# waterlevel.net
KiCad netlist of a schematic drawn in EAGLE
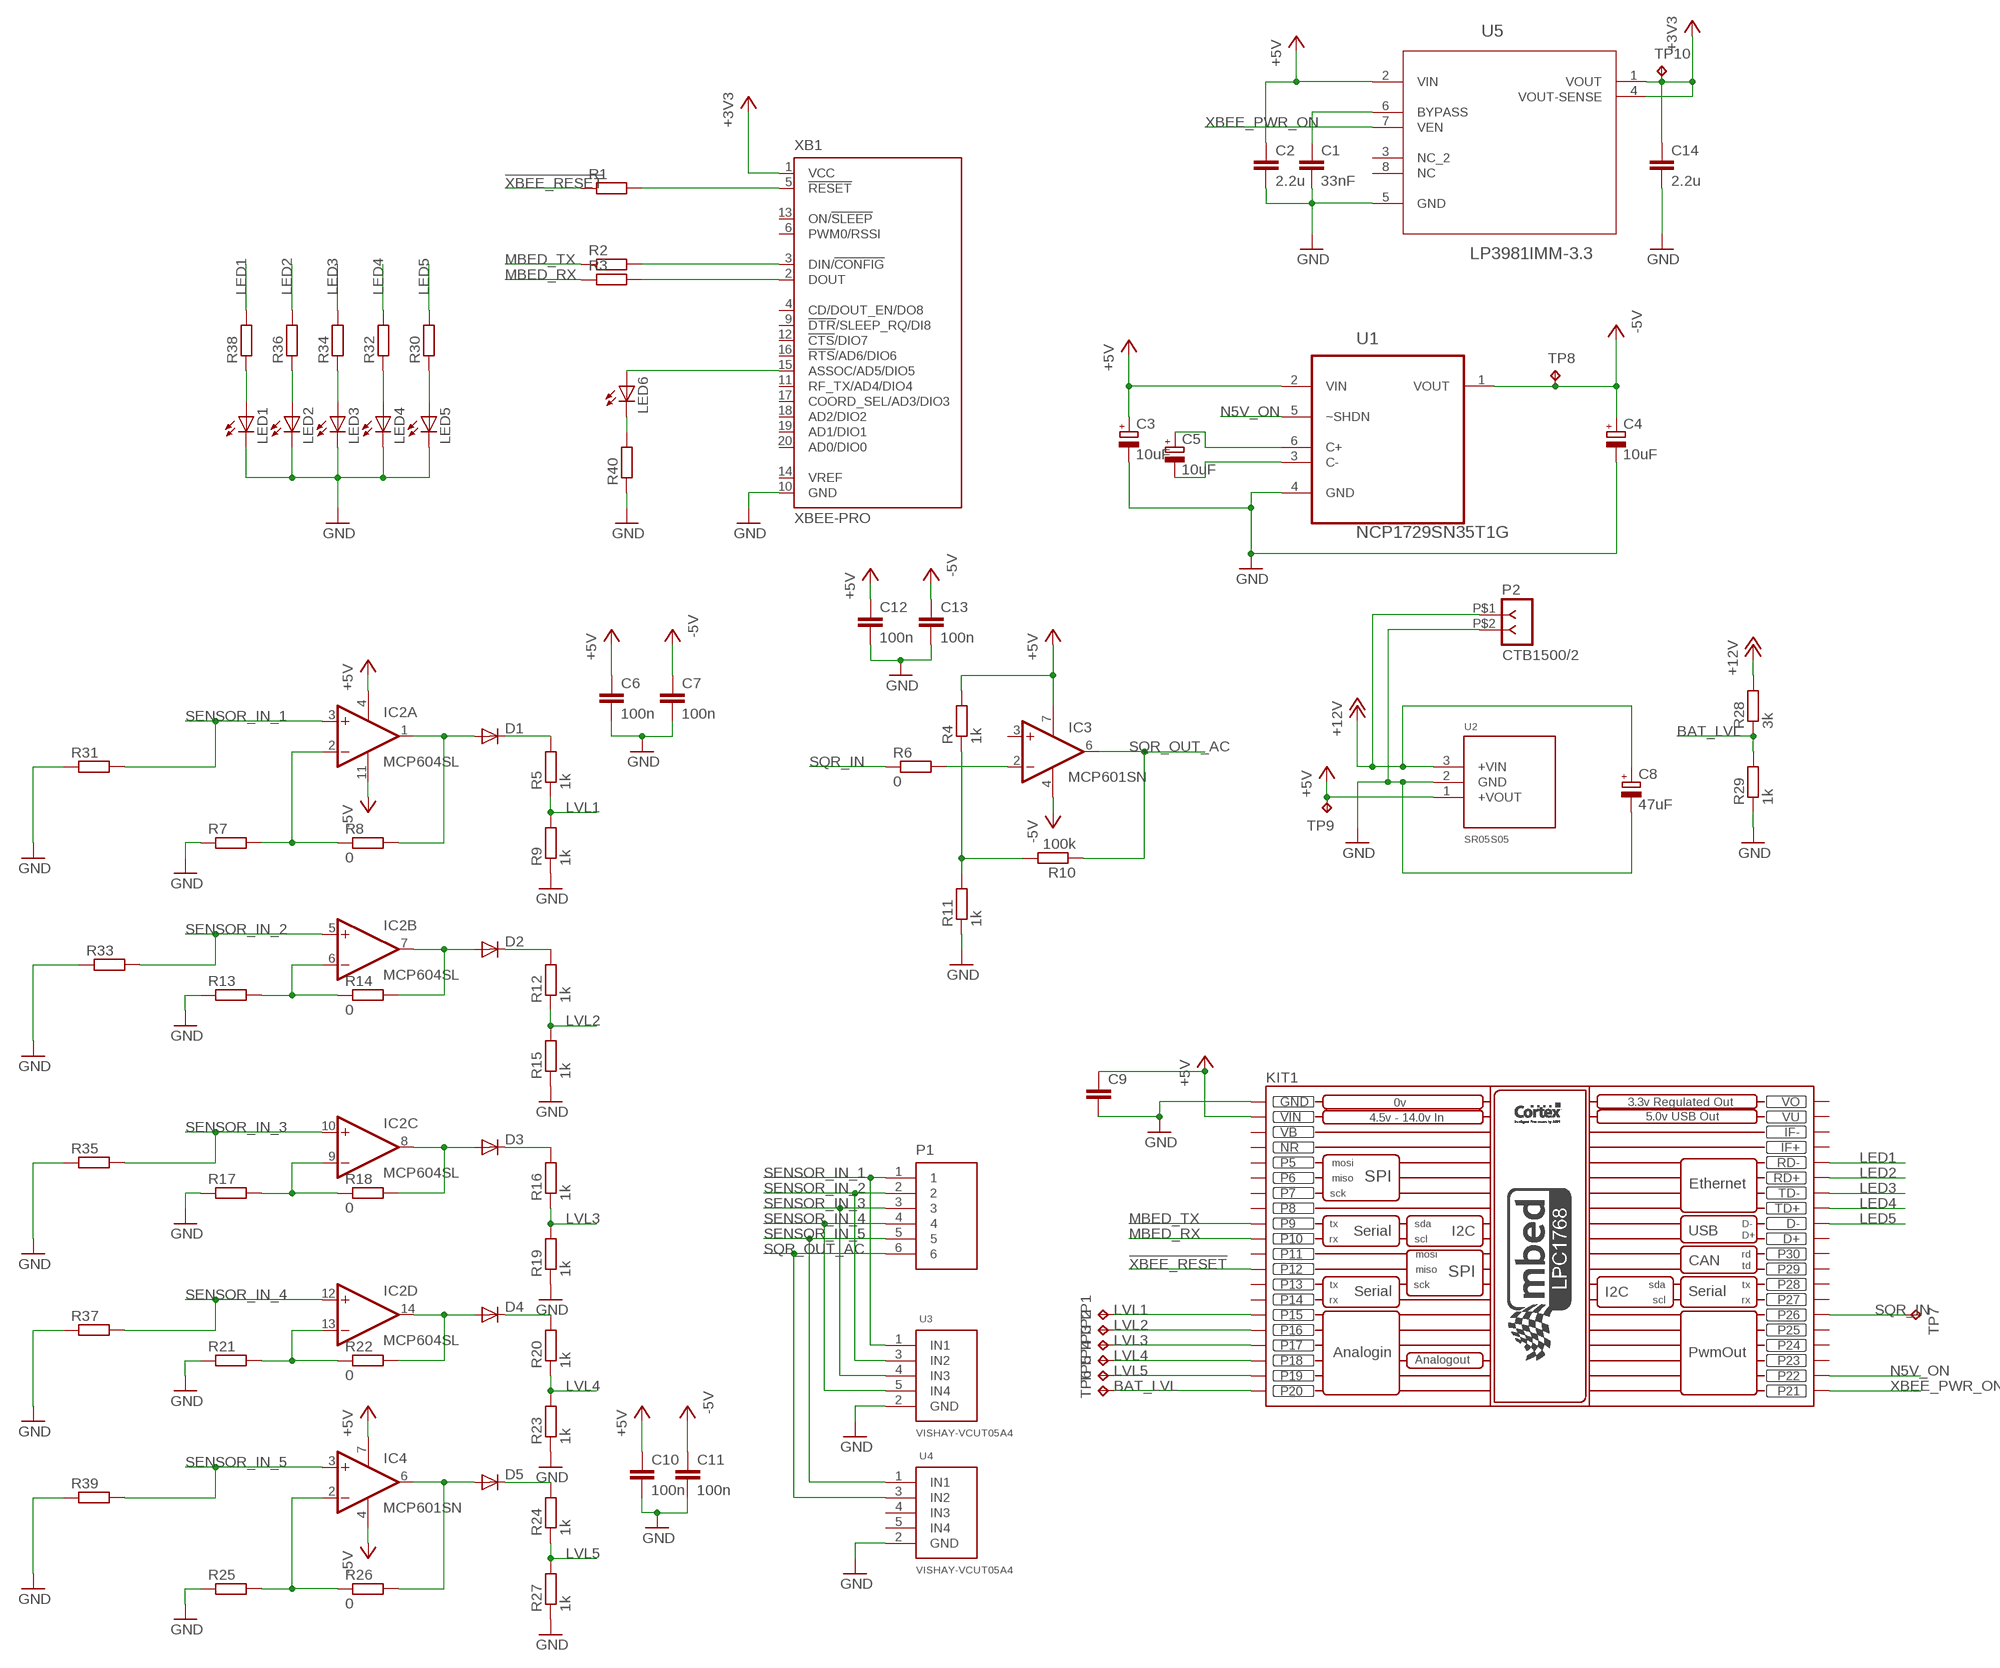
[diagram p0: schematic, sheet 1]

(export (version "E")
  (design (tool "Eeschema 10.0.6"))
  (components
    (comp (ref "C1")
      (value "33nF")
      (footprint "eagle-import:C0603")
      (libsource (lib "eagle-import") (part "C-EUC0603"))
    )
    (comp (ref "C2")
      (value "2.2u")
      (footprint "eagle-import:C0603")
      (libsource (lib "eagle-import") (part "C-EUC0603"))
    )
    (comp (ref "C3")
      (value "10uF")
      (footprint "eagle-import:D_7343-31R")
      (libsource (lib "eagle-import") (part "CPOL-EUD/7343-31R"))
    )
    (comp (ref "C4")
      (value "10uF")
      (footprint "eagle-import:D_7343-31R")
      (libsource (lib "eagle-import") (part "CPOL-EUD/7343-31R"))
    )
    (comp (ref "C5")
      (value "10uF")
      (footprint "eagle-import:D_7343-31R")
      (libsource (lib "eagle-import") (part "CPOL-EUD/7343-31R"))
    )
    (comp (ref "C6")
      (value "100n")
      (footprint "eagle-import:C1206")
      (libsource (lib "eagle-import") (part "C-EUC1206"))
    )
    (comp (ref "C7")
      (value "100n")
      (footprint "eagle-import:C1206")
      (libsource (lib "eagle-import") (part "C-EUC1206"))
    )
    (comp (ref "C8")
      (value "47uF")
      (footprint "eagle-import:D_7343-31R")
      (libsource (lib "eagle-import") (part "CPOL-EUD/7343-31R"))
    )
    (comp (ref "C9")
      (value "C-EUC1206")
      (footprint "eagle-import:C1206")
      (libsource (lib "eagle-import") (part "C-EUC1206"))
    )
    (comp (ref "C10")
      (value "100n")
      (footprint "eagle-import:C1206")
      (libsource (lib "eagle-import") (part "C-EUC1206"))
    )
    (comp (ref "C11")
      (value "100n")
      (footprint "eagle-import:C1206")
      (libsource (lib "eagle-import") (part "C-EUC1206"))
    )
    (comp (ref "C12")
      (value "100n")
      (footprint "eagle-import:C1206")
      (libsource (lib "eagle-import") (part "C-EUC1206"))
    )
    (comp (ref "C13")
      (value "100n")
      (footprint "eagle-import:C1206")
      (libsource (lib "eagle-import") (part "C-EUC1206"))
    )
    (comp (ref "C14")
      (value "2.2u")
      (footprint "eagle-import:C0603")
      (libsource (lib "eagle-import") (part "C-EUC0603"))
    )
    (comp (ref "D1")
      (value "DIODE-SOD323-R")
      (footprint "eagle-import:SOD323-R")
      (fields (field (name "PART") "RB751V40"))
      (libsource (lib "eagle-import") (part "DIODE-SOD323-R"))
    )
    (comp (ref "D2")
      (value "DIODE-SOD323-R")
      (footprint "eagle-import:SOD323-R")
      (fields (field (name "PART") "RB751V40"))
      (libsource (lib "eagle-import") (part "DIODE-SOD323-R"))
    )
    (comp (ref "D3")
      (value "DIODE-SOD323-R")
      (footprint "eagle-import:SOD323-R")
      (fields (field (name "PART") "RB751V40"))
      (libsource (lib "eagle-import") (part "DIODE-SOD323-R"))
    )
    (comp (ref "D4")
      (value "DIODE-SOD323-R")
      (footprint "eagle-import:SOD323-R")
      (fields (field (name "PART") "RB751V40"))
      (libsource (lib "eagle-import") (part "DIODE-SOD323-R"))
    )
    (comp (ref "D5")
      (value "DIODE-SOD323-R")
      (footprint "eagle-import:SOD323-R")
      (fields (field (name "PART") "RB751V40"))
      (libsource (lib "eagle-import") (part "DIODE-SOD323-R"))
    )
    (comp (ref "IC2")
      (value "MCP604SL")
      (footprint "eagle-import:SO14")
      (libsource (lib "eagle-import") (part "MCP604SL"))
    )
    (comp (ref "IC3")
      (value "MCP601SN")
      (footprint "eagle-import:SO08")
      (libsource (lib "eagle-import") (part "MCP601SN"))
    )
    (comp (ref "IC4")
      (value "MCP601SN")
      (footprint "eagle-import:SO08")
      (libsource (lib "eagle-import") (part "MCP601SN"))
    )
    (comp (ref "KIT1")
      (value "MBED_NXP_LPC1768")
      (footprint "eagle-import:MBED-KIT")
      (libsource (lib "eagle-import") (part "MBED_NXP_LPC1768"))
    )
    (comp (ref "LED1")
      (value "LEDCHIPLED_0805")
      (footprint "eagle-import:CHIPLED_0805")
      (libsource (lib "eagle-import") (part "LEDCHIPLED_0805"))
    )
    (comp (ref "LED2")
      (value "LEDCHIPLED_0805")
      (footprint "eagle-import:CHIPLED_0805")
      (libsource (lib "eagle-import") (part "LEDCHIPLED_0805"))
    )
    (comp (ref "LED3")
      (value "LEDCHIPLED_0805")
      (footprint "eagle-import:CHIPLED_0805")
      (libsource (lib "eagle-import") (part "LEDCHIPLED_0805"))
    )
    (comp (ref "LED4")
      (value "LEDCHIPLED_0805")
      (footprint "eagle-import:CHIPLED_0805")
      (libsource (lib "eagle-import") (part "LEDCHIPLED_0805"))
    )
    (comp (ref "LED5")
      (value "LEDCHIPLED_0805")
      (footprint "eagle-import:CHIPLED_0805")
      (libsource (lib "eagle-import") (part "LEDCHIPLED_0805"))
    )
    (comp (ref "LED6")
      (value "LEDCHIPLED_0805")
      (footprint "eagle-import:CHIPLED_0805")
      (libsource (lib "eagle-import") (part "LEDCHIPLED_0805"))
    )
    (comp (ref "P1")
      (value "CAMDEN-CTB5000/6")
      (footprint "eagle-import:CAMDEN-CTB5000")
      (libsource (lib "eagle-import") (part "CAMDEN-CTB5000/6"))
    )
    (comp (ref "P2")
      (value "CTB1500/2")
      (footprint "eagle-import:CTB1500-2")
      (libsource (lib "eagle-import") (part "CTB1500/2"))
    )
    (comp (ref "R1")
      (value "R-EU_R0603")
      (footprint "eagle-import:R0603")
      (libsource (lib "eagle-import") (part "R-EU_R0603"))
    )
    (comp (ref "R2")
      (value "R-EU_R0603")
      (footprint "eagle-import:R0603")
      (libsource (lib "eagle-import") (part "R-EU_R0603"))
    )
    (comp (ref "R3")
      (value "R-EU_R0603")
      (footprint "eagle-import:R0603")
      (libsource (lib "eagle-import") (part "R-EU_R0603"))
    )
    (comp (ref "R4")
      (value "1k")
      (footprint "eagle-import:R0805")
      (libsource (lib "eagle-import") (part "R-EU_R0805"))
    )
    (comp (ref "R5")
      (value "1k")
      (footprint "eagle-import:R0805")
      (libsource (lib "eagle-import") (part "R-EU_R0805"))
    )
    (comp (ref "R6")
      (value "0")
      (footprint "eagle-import:R0603")
      (libsource (lib "eagle-import") (part "R-EU_R0603"))
    )
    (comp (ref "R7")
      (value "R-EU_R0603")
      (footprint "eagle-import:R0603")
      (libsource (lib "eagle-import") (part "R-EU_R0603"))
    )
    (comp (ref "R8")
      (value "0")
      (footprint "eagle-import:R0603")
      (libsource (lib "eagle-import") (part "R-EU_R0603"))
    )
    (comp (ref "R9")
      (value "1k")
      (footprint "eagle-import:R0805")
      (libsource (lib "eagle-import") (part "R-EU_R0805"))
    )
    (comp (ref "R10")
      (value "100k")
      (footprint "eagle-import:R0805")
      (libsource (lib "eagle-import") (part "R-EU_R0805"))
    )
    (comp (ref "R11")
      (value "1k")
      (footprint "eagle-import:R0805")
      (libsource (lib "eagle-import") (part "R-EU_R0805"))
    )
    (comp (ref "R12")
      (value "1k")
      (footprint "eagle-import:R0805")
      (libsource (lib "eagle-import") (part "R-EU_R0805"))
    )
    (comp (ref "R13")
      (value "R-EU_R0603")
      (footprint "eagle-import:R0603")
      (libsource (lib "eagle-import") (part "R-EU_R0603"))
    )
    (comp (ref "R14")
      (value "0")
      (footprint "eagle-import:R0603")
      (libsource (lib "eagle-import") (part "R-EU_R0603"))
    )
    (comp (ref "R15")
      (value "1k")
      (footprint "eagle-import:R0805")
      (libsource (lib "eagle-import") (part "R-EU_R0805"))
    )
    (comp (ref "R16")
      (value "1k")
      (footprint "eagle-import:R0805")
      (libsource (lib "eagle-import") (part "R-EU_R0805"))
    )
    (comp (ref "R17")
      (value "R-EU_R0603")
      (footprint "eagle-import:R0603")
      (libsource (lib "eagle-import") (part "R-EU_R0603"))
    )
    (comp (ref "R18")
      (value "0")
      (footprint "eagle-import:R0603")
      (libsource (lib "eagle-import") (part "R-EU_R0603"))
    )
    (comp (ref "R19")
      (value "1k")
      (footprint "eagle-import:R0805")
      (libsource (lib "eagle-import") (part "R-EU_R0805"))
    )
    (comp (ref "R20")
      (value "1k")
      (footprint "eagle-import:R0805")
      (libsource (lib "eagle-import") (part "R-EU_R0805"))
    )
    (comp (ref "R21")
      (value "R-EU_R0603")
      (footprint "eagle-import:R0603")
      (libsource (lib "eagle-import") (part "R-EU_R0603"))
    )
    (comp (ref "R22")
      (value "0")
      (footprint "eagle-import:R0603")
      (libsource (lib "eagle-import") (part "R-EU_R0603"))
    )
    (comp (ref "R23")
      (value "1k")
      (footprint "eagle-import:R0805")
      (libsource (lib "eagle-import") (part "R-EU_R0805"))
    )
    (comp (ref "R24")
      (value "1k")
      (footprint "eagle-import:R0805")
      (libsource (lib "eagle-import") (part "R-EU_R0805"))
    )
    (comp (ref "R25")
      (value "R-EU_R0603")
      (footprint "eagle-import:R0603")
      (libsource (lib "eagle-import") (part "R-EU_R0603"))
    )
    (comp (ref "R26")
      (value "0")
      (footprint "eagle-import:R0603")
      (libsource (lib "eagle-import") (part "R-EU_R0603"))
    )
    (comp (ref "R27")
      (value "1k")
      (footprint "eagle-import:R0805")
      (libsource (lib "eagle-import") (part "R-EU_R0805"))
    )
    (comp (ref "R28")
      (value "3k")
      (footprint "eagle-import:R0805")
      (libsource (lib "eagle-import") (part "R-EU_R0805"))
    )
    (comp (ref "R29")
      (value "1k")
      (footprint "eagle-import:R0805")
      (libsource (lib "eagle-import") (part "R-EU_R0805"))
    )
    (comp (ref "R30")
      (value "R-EU_R0603")
      (footprint "eagle-import:R0603")
      (libsource (lib "eagle-import") (part "R-EU_R0603"))
    )
    (comp (ref "R31")
      (value "R-EU_R0805")
      (footprint "eagle-import:R0805")
      (libsource (lib "eagle-import") (part "R-EU_R0805"))
    )
    (comp (ref "R32")
      (value "R-EU_R0603")
      (footprint "eagle-import:R0603")
      (libsource (lib "eagle-import") (part "R-EU_R0603"))
    )
    (comp (ref "R33")
      (value "R-EU_R0805")
      (footprint "eagle-import:R0805")
      (libsource (lib "eagle-import") (part "R-EU_R0805"))
    )
    (comp (ref "R34")
      (value "R-EU_R0603")
      (footprint "eagle-import:R0603")
      (libsource (lib "eagle-import") (part "R-EU_R0603"))
    )
    (comp (ref "R35")
      (value "R-EU_R0805")
      (footprint "eagle-import:R0805")
      (libsource (lib "eagle-import") (part "R-EU_R0805"))
    )
    (comp (ref "R36")
      (value "R-EU_R0603")
      (footprint "eagle-import:R0603")
      (libsource (lib "eagle-import") (part "R-EU_R0603"))
    )
    (comp (ref "R37")
      (value "R-EU_R0805")
      (footprint "eagle-import:R0805")
      (libsource (lib "eagle-import") (part "R-EU_R0805"))
    )
    (comp (ref "R38")
      (value "R-EU_R0603")
      (footprint "eagle-import:R0603")
      (libsource (lib "eagle-import") (part "R-EU_R0603"))
    )
    (comp (ref "R39")
      (value "R-EU_R0805")
      (footprint "eagle-import:R0805")
      (libsource (lib "eagle-import") (part "R-EU_R0805"))
    )
    (comp (ref "R40")
      (value "R-EU_R0603")
      (footprint "eagle-import:R0603")
      (libsource (lib "eagle-import") (part "R-EU_R0603"))
    )
    (comp (ref "TP1")
      (value "TPTP13R")
      (footprint "eagle-import:TP13R")
      (libsource (lib "eagle-import") (part "TPTP13R"))
    )
    (comp (ref "TP2")
      (value "TPTP13R")
      (footprint "eagle-import:TP13R")
      (libsource (lib "eagle-import") (part "TPTP13R"))
    )
    (comp (ref "TP3")
      (value "TPTP13R")
      (footprint "eagle-import:TP13R")
      (libsource (lib "eagle-import") (part "TPTP13R"))
    )
    (comp (ref "TP4")
      (value "TPTP13R")
      (footprint "eagle-import:TP13R")
      (libsource (lib "eagle-import") (part "TPTP13R"))
    )
    (comp (ref "TP5")
      (value "TPTP13R")
      (footprint "eagle-import:TP13R")
      (libsource (lib "eagle-import") (part "TPTP13R"))
    )
    (comp (ref "TP6")
      (value "TPTP13R")
      (footprint "eagle-import:TP13R")
      (libsource (lib "eagle-import") (part "TPTP13R"))
    )
    (comp (ref "TP7")
      (value "TPTP13R")
      (footprint "eagle-import:TP13R")
      (libsource (lib "eagle-import") (part "TPTP13R"))
    )
    (comp (ref "TP8")
      (value "TPTP13R")
      (footprint "eagle-import:TP13R")
      (libsource (lib "eagle-import") (part "TPTP13R"))
    )
    (comp (ref "TP9")
      (value "TPTP13R")
      (footprint "eagle-import:TP13R")
      (libsource (lib "eagle-import") (part "TPTP13R"))
    )
    (comp (ref "TP10")
      (value "TPTP13R")
      (footprint "eagle-import:TP13R")
      (libsource (lib "eagle-import") (part "TPTP13R"))
    )
    (comp (ref "U1")
      (value "NCP1729SN35T1G")
      (footprint "eagle-import:SOP95P275X110-6N")
      (libsource (lib "eagle-import") (part "NCP1729SN35T1G"))
    )
    (comp (ref "U2")
      (value "SR05S05")
      (footprint "eagle-import:XP-SR-SERIES")
      (libsource (lib "eagle-import") (part "SR05S05"))
    )
    (comp (ref "U3")
      (value "VISHAY-VCUT05A4")
      (footprint "eagle-import:SOT23-5")
      (libsource (lib "eagle-import") (part "VISHAY-VCUT05A4"))
    )
    (comp (ref "U4")
      (value "VISHAY-VCUT05A4")
      (footprint "eagle-import:SOT23-5")
      (libsource (lib "eagle-import") (part "VISHAY-VCUT05A4"))
    )
    (comp (ref "U5")
      (value "LP3981IMM-3.3")
      (footprint "eagle-import:SOP65P490X110-8N")
      (libsource (lib "eagle-import") (part "LP3981IMM-3.3"))
    )
    (comp (ref "XB1")
      (value "XBEE-PRO")
      (footprint "eagle-import:XBEE-PRO")
      (fields (field (name "MPN") "XBP24-AWI-001"))
      (libsource (lib "eagle-import") (part "XBEE-PRO"))
    )
  )
  (nets
    (net (code "1") (name "+3V3") (class "Default")
      (node (ref "C14") (pin "1") (pinfunction "1_1") (pintype "passive"))
      (node (ref "TP10") (pin "TP") (pinfunction "TP_TP") (pintype "input"))
      (node (ref "U5") (pin "1") (pinfunction "VOUT_1") (pintype "output"))
      (node (ref "U5") (pin "4") (pinfunction "VOUT-SENSE_4") (pintype "output"))
      (node (ref "XB1") (pin "1") (pinfunction "VCC_1") (pintype "power_in"))
    )
    (net (code "2") (name "+5V") (class "Default")
      (node (ref "C10") (pin "1") (pinfunction "1_1") (pintype "passive"))
      (node (ref "C12") (pin "1") (pinfunction "1_1") (pintype "passive"))
      (node (ref "C2") (pin "1") (pinfunction "1_1") (pintype "passive"))
      (node (ref "C3") (pin "+") (pinfunction "+_+") (pintype "passive"))
      (node (ref "C6") (pin "1") (pinfunction "1_1") (pintype "passive"))
      (node (ref "C9") (pin "1") (pinfunction "1_1") (pintype "passive"))
      (node (ref "IC2") (pin "4") (pinfunction "V+_4") (pintype "power_in"))
      (node (ref "IC3") (pin "7") (pinfunction "V+_7") (pintype "power_in"))
      (node (ref "IC4") (pin "7") (pinfunction "V+_7") (pintype "power_in"))
      (node (ref "KIT1") (pin "VIN") (pinfunction "VIN_VIN") (pintype "power_in"))
      (node (ref "R4") (pin "2") (pinfunction "2_2") (pintype "passive"))
      (node (ref "TP9") (pin "TP") (pinfunction "TP_TP") (pintype "input"))
      (node (ref "U1") (pin "2") (pinfunction "VIN_2") (pintype "power_in"))
      (node (ref "U2") (pin "1") (pinfunction "+VOUT_1") (pintype "bidirectional"))
      (node (ref "U5") (pin "2") (pinfunction "VIN_2") (pintype "input"))
    )
    (net (code "3") (name "+12V") (class "Default")
      (node (ref "C8") (pin "+") (pinfunction "+_+") (pintype "passive"))
      (node (ref "P2") (pin "P$1") (pinfunction "1_P$1") (pintype "passive"))
      (node (ref "R28") (pin "2") (pinfunction "2_2") (pintype "passive"))
      (node (ref "U2") (pin "3") (pinfunction "+VIN_3") (pintype "bidirectional"))
    )
    (net (code "4") (name "-5V") (class "Default")
      (node (ref "C11") (pin "1") (pinfunction "1_1") (pintype "passive"))
      (node (ref "C13") (pin "1") (pinfunction "1_1") (pintype "passive"))
      (node (ref "C4") (pin "+") (pinfunction "+_+") (pintype "passive"))
      (node (ref "C7") (pin "1") (pinfunction "1_1") (pintype "passive"))
      (node (ref "IC2") (pin "11") (pinfunction "V-_11") (pintype "power_in"))
      (node (ref "IC3") (pin "4") (pinfunction "V-_4") (pintype "power_in"))
      (node (ref "IC4") (pin "4") (pinfunction "V-_4") (pintype "power_in"))
      (node (ref "TP8") (pin "TP") (pinfunction "TP_TP") (pintype "input"))
      (node (ref "U1") (pin "1") (pinfunction "VOUT_1") (pintype "output"))
    )
    (net (code "5") (name "/BAT_LVL") (class "Default")
      (node (ref "KIT1") (pin "P$20") (pinfunction "P20_P$20") (pintype "bidirectional"))
      (node (ref "R28") (pin "1") (pinfunction "1_1") (pintype "passive"))
      (node (ref "R29") (pin "2") (pinfunction "2_2") (pintype "passive"))
      (node (ref "TP6") (pin "TP") (pinfunction "TP_TP") (pintype "input"))
    )
    (net (code "6") (name "/LED1") (class "Default")
      (node (ref "KIT1") (pin "RD-") (pinfunction "RD-_RD-") (pintype "bidirectional"))
      (node (ref "R38") (pin "2") (pinfunction "2_2") (pintype "passive"))
    )
    (net (code "7") (name "/LED2") (class "Default")
      (node (ref "KIT1") (pin "RD+") (pinfunction "RD+_RD+") (pintype "bidirectional"))
      (node (ref "R36") (pin "2") (pinfunction "2_2") (pintype "passive"))
    )
    (net (code "8") (name "/LED3") (class "Default")
      (node (ref "KIT1") (pin "TD-") (pinfunction "TD-_TD-") (pintype "bidirectional"))
      (node (ref "R34") (pin "2") (pinfunction "2_2") (pintype "passive"))
    )
    (net (code "9") (name "/LED4") (class "Default")
      (node (ref "KIT1") (pin "TD+") (pinfunction "TD+_TD+") (pintype "bidirectional"))
      (node (ref "R32") (pin "2") (pinfunction "2_2") (pintype "passive"))
    )
    (net (code "10") (name "/LED5") (class "Default")
      (node (ref "KIT1") (pin "D-") (pinfunction "D-_D-") (pintype "bidirectional"))
      (node (ref "R30") (pin "2") (pinfunction "2_2") (pintype "passive"))
    )
    (net (code "11") (name "/LVL1") (class "Default")
      (node (ref "KIT1") (pin "P$15") (pinfunction "P15_P$15") (pintype "bidirectional"))
      (node (ref "R5") (pin "1") (pinfunction "1_1") (pintype "passive"))
      (node (ref "R9") (pin "2") (pinfunction "2_2") (pintype "passive"))
      (node (ref "TP1") (pin "TP") (pinfunction "TP_TP") (pintype "input"))
    )
    (net (code "12") (name "/LVL2") (class "Default")
      (node (ref "KIT1") (pin "P$16") (pinfunction "P16_P$16") (pintype "bidirectional"))
      (node (ref "R12") (pin "1") (pinfunction "1_1") (pintype "passive"))
      (node (ref "R15") (pin "2") (pinfunction "2_2") (pintype "passive"))
      (node (ref "TP2") (pin "TP") (pinfunction "TP_TP") (pintype "input"))
    )
    (net (code "13") (name "/LVL3") (class "Default")
      (node (ref "KIT1") (pin "P$17") (pinfunction "P17_P$17") (pintype "bidirectional"))
      (node (ref "R16") (pin "1") (pinfunction "1_1") (pintype "passive"))
      (node (ref "R19") (pin "2") (pinfunction "2_2") (pintype "passive"))
      (node (ref "TP3") (pin "TP") (pinfunction "TP_TP") (pintype "input"))
    )
    (net (code "14") (name "/LVL4") (class "Default")
      (node (ref "KIT1") (pin "P$18") (pinfunction "P18_P$18") (pintype "bidirectional"))
      (node (ref "R20") (pin "1") (pinfunction "1_1") (pintype "passive"))
      (node (ref "R23") (pin "2") (pinfunction "2_2") (pintype "passive"))
      (node (ref "TP4") (pin "TP") (pinfunction "TP_TP") (pintype "input"))
    )
    (net (code "15") (name "/LVL5") (class "Default")
      (node (ref "KIT1") (pin "P$19") (pinfunction "P19_P$19") (pintype "bidirectional"))
      (node (ref "R24") (pin "1") (pinfunction "1_1") (pintype "passive"))
      (node (ref "R27") (pin "2") (pinfunction "2_2") (pintype "passive"))
      (node (ref "TP5") (pin "TP") (pinfunction "TP_TP") (pintype "input"))
    )
    (net (code "16") (name "/MBED_RX") (class "Default")
      (node (ref "KIT1") (pin "P$10") (pinfunction "P10_P$10") (pintype "bidirectional"))
      (node (ref "R3") (pin "1") (pinfunction "1_1") (pintype "passive"))
    )
    (net (code "17") (name "/MBED_TX") (class "Default")
      (node (ref "KIT1") (pin "P$9") (pinfunction "P9_P$9") (pintype "bidirectional"))
      (node (ref "R2") (pin "1") (pinfunction "1_1") (pintype "passive"))
    )
    (net (code "18") (name "/N5V_ON") (class "Default")
      (node (ref "KIT1") (pin "P$22") (pinfunction "P22_P$22") (pintype "bidirectional"))
      (node (ref "U1") (pin "5") (pinfunction "~{SHDN}_5") (pintype "input"))
    )
    (net (code "19") (name "/NR") (class "Default")
      (node (ref "KIT1") (pin "NR") (pinfunction "NR_NR") (pintype "power_in"))
    )
    (net (code "20") (name "/SENSOR_IN_1") (class "Default")
      (node (ref "IC2") (pin "3") (pinfunction "+IN_3") (pintype "input"))
      (node (ref "P1") (pin "1") (pinfunction "1_1") (pintype "bidirectional"))
      (node (ref "R31") (pin "2") (pinfunction "2_2") (pintype "passive"))
      (node (ref "U3") (pin "1") (pinfunction "IN1_1") (pintype "bidirectional"))
    )
    (net (code "21") (name "/SENSOR_IN_2") (class "Default")
      (node (ref "IC2") (pin "5") (pinfunction "+IN_5") (pintype "input"))
      (node (ref "P1") (pin "2") (pinfunction "2_2") (pintype "bidirectional"))
      (node (ref "R33") (pin "2") (pinfunction "2_2") (pintype "passive"))
      (node (ref "U3") (pin "3") (pinfunction "IN2_3") (pintype "bidirectional"))
    )
    (net (code "22") (name "/SENSOR_IN_3") (class "Default")
      (node (ref "IC2") (pin "10") (pinfunction "+IN_10") (pintype "input"))
      (node (ref "P1") (pin "3") (pinfunction "3_3") (pintype "bidirectional"))
      (node (ref "R35") (pin "2") (pinfunction "2_2") (pintype "passive"))
      (node (ref "U3") (pin "4") (pinfunction "IN3_4") (pintype "bidirectional"))
    )
    (net (code "23") (name "/SENSOR_IN_4") (class "Default")
      (node (ref "IC2") (pin "12") (pinfunction "+IN_12") (pintype "input"))
      (node (ref "P1") (pin "4") (pinfunction "4_4") (pintype "bidirectional"))
      (node (ref "R37") (pin "2") (pinfunction "2_2") (pintype "passive"))
      (node (ref "U3") (pin "5") (pinfunction "IN4_5") (pintype "bidirectional"))
    )
    (net (code "24") (name "/SENSOR_IN_5") (class "Default")
      (node (ref "IC4") (pin "3") (pinfunction "+IN_3") (pintype "input"))
      (node (ref "P1") (pin "5") (pinfunction "5_5") (pintype "bidirectional"))
      (node (ref "R39") (pin "2") (pinfunction "2_2") (pintype "passive"))
      (node (ref "U4") (pin "1") (pinfunction "IN1_1") (pintype "bidirectional"))
    )
    (net (code "25") (name "/SQR_IN") (class "Default")
      (node (ref "KIT1") (pin "P$26") (pinfunction "P26_P$26") (pintype "bidirectional"))
      (node (ref "R6") (pin "1") (pinfunction "1_1") (pintype "passive"))
      (node (ref "TP7") (pin "TP") (pinfunction "TP_TP") (pintype "input"))
    )
    (net (code "26") (name "/SQR_OUT_AC") (class "Default")
      (node (ref "IC3") (pin "6") (pinfunction "OUT_6") (pintype "output"))
      (node (ref "P1") (pin "6") (pinfunction "6_6") (pintype "bidirectional"))
      (node (ref "R10") (pin "1") (pinfunction "1_1") (pintype "passive"))
      (node (ref "U4") (pin "3") (pinfunction "IN2_3") (pintype "bidirectional"))
    )
    (net (code "27") (name "/VB") (class "Default")
      (node (ref "KIT1") (pin "VB") (pinfunction "VB_VB") (pintype "power_in"))
    )
    (net (code "28") (name "/VO") (class "Default")
      (node (ref "KIT1") (pin "VOUT") (pinfunction "VO_VOUT") (pintype "power_in"))
    )
    (net (code "29") (name "/VU") (class "Default")
      (node (ref "KIT1") (pin "VU") (pinfunction "VU_VU") (pintype "power_in"))
    )
    (net (code "30") (name "/XBEE_PWR_ON") (class "Default")
      (node (ref "KIT1") (pin "P$21") (pinfunction "P21_P$21") (pintype "bidirectional"))
      (node (ref "U5") (pin "7") (pinfunction "VEN_7") (pintype "input"))
    )
    (net (code "31") (name "/~{XBEE_RESET}") (class "Default")
      (node (ref "KIT1") (pin "P$12") (pinfunction "P12_P$12") (pintype "bidirectional"))
      (node (ref "R1") (pin "1") (pinfunction "1_1") (pintype "passive"))
    )
    (net (code "32") (name "GND") (class "Default")
      (node (ref "C1") (pin "2") (pinfunction "2_2") (pintype "passive"))
      (node (ref "C10") (pin "2") (pinfunction "2_2") (pintype "passive"))
      (node (ref "C11") (pin "2") (pinfunction "2_2") (pintype "passive"))
      (node (ref "C12") (pin "2") (pinfunction "2_2") (pintype "passive"))
      (node (ref "C13") (pin "2") (pinfunction "2_2") (pintype "passive"))
      (node (ref "C14") (pin "2") (pinfunction "2_2") (pintype "passive"))
      (node (ref "C2") (pin "2") (pinfunction "2_2") (pintype "passive"))
      (node (ref "C3") (pin "-") (pinfunction "-_-") (pintype "passive"))
      (node (ref "C4") (pin "-") (pinfunction "-_-") (pintype "passive"))
      (node (ref "C6") (pin "2") (pinfunction "2_2") (pintype "passive"))
      (node (ref "C7") (pin "2") (pinfunction "2_2") (pintype "passive"))
      (node (ref "C8") (pin "-") (pinfunction "-_-") (pintype "passive"))
      (node (ref "C9") (pin "2") (pinfunction "2_2") (pintype "passive"))
      (node (ref "KIT1") (pin "GND") (pinfunction "GND_GND") (pintype "power_in"))
      (node (ref "LED1") (pin "C") (pinfunction "C_C") (pintype "passive"))
      (node (ref "LED2") (pin "C") (pinfunction "C_C") (pintype "passive"))
      (node (ref "LED3") (pin "C") (pinfunction "C_C") (pintype "passive"))
      (node (ref "LED4") (pin "C") (pinfunction "C_C") (pintype "passive"))
      (node (ref "LED5") (pin "C") (pinfunction "C_C") (pintype "passive"))
      (node (ref "P2") (pin "P$2") (pinfunction "2_P$2") (pintype "passive"))
      (node (ref "R11") (pin "1") (pinfunction "1_1") (pintype "passive"))
      (node (ref "R13") (pin "1") (pinfunction "1_1") (pintype "passive"))
      (node (ref "R15") (pin "1") (pinfunction "1_1") (pintype "passive"))
      (node (ref "R17") (pin "1") (pinfunction "1_1") (pintype "passive"))
      (node (ref "R19") (pin "1") (pinfunction "1_1") (pintype "passive"))
      (node (ref "R21") (pin "1") (pinfunction "1_1") (pintype "passive"))
      (node (ref "R23") (pin "1") (pinfunction "1_1") (pintype "passive"))
      (node (ref "R25") (pin "1") (pinfunction "1_1") (pintype "passive"))
      (node (ref "R27") (pin "1") (pinfunction "1_1") (pintype "passive"))
      (node (ref "R29") (pin "1") (pinfunction "1_1") (pintype "passive"))
      (node (ref "R31") (pin "1") (pinfunction "1_1") (pintype "passive"))
      (node (ref "R33") (pin "1") (pinfunction "1_1") (pintype "passive"))
      (node (ref "R35") (pin "1") (pinfunction "1_1") (pintype "passive"))
      (node (ref "R37") (pin "1") (pinfunction "1_1") (pintype "passive"))
      (node (ref "R39") (pin "1") (pinfunction "1_1") (pintype "passive"))
      (node (ref "R40") (pin "1") (pinfunction "1_1") (pintype "passive"))
      (node (ref "R7") (pin "1") (pinfunction "1_1") (pintype "passive"))
      (node (ref "R9") (pin "1") (pinfunction "1_1") (pintype "passive"))
      (node (ref "U1") (pin "4") (pinfunction "GND_4") (pintype "passive"))
      (node (ref "U2") (pin "2") (pinfunction "GND_2") (pintype "bidirectional"))
      (node (ref "U3") (pin "2") (pinfunction "GND_2") (pintype "bidirectional"))
      (node (ref "U4") (pin "2") (pinfunction "GND_2") (pintype "bidirectional"))
      (node (ref "U5") (pin "5") (pinfunction "GND_5") (pintype "passive"))
      (node (ref "XB1") (pin "10") (pinfunction "GND_10") (pintype "power_in"))
    )
    (net (code "33") (name "Net-(D1-PadC)") (class "Default")
      (node (ref "D1") (pin "C") (pinfunction "C_C") (pintype "passive"))
      (node (ref "R5") (pin "2") (pinfunction "2_2") (pintype "passive"))
    )
    (net (code "34") (name "Net-(D2-PadC)") (class "Default")
      (node (ref "D2") (pin "C") (pinfunction "C_C") (pintype "passive"))
      (node (ref "R12") (pin "2") (pinfunction "2_2") (pintype "passive"))
    )
    (net (code "35") (name "Net-(D3-PadC)") (class "Default")
      (node (ref "D3") (pin "C") (pinfunction "C_C") (pintype "passive"))
      (node (ref "R16") (pin "2") (pinfunction "2_2") (pintype "passive"))
    )
    (net (code "36") (name "Net-(D4-PadC)") (class "Default")
      (node (ref "D4") (pin "C") (pinfunction "C_C") (pintype "passive"))
      (node (ref "R20") (pin "2") (pinfunction "2_2") (pintype "passive"))
    )
    (net (code "37") (name "Net-(D5-PadC)") (class "Default")
      (node (ref "D5") (pin "C") (pinfunction "C_C") (pintype "passive"))
      (node (ref "R24") (pin "2") (pinfunction "2_2") (pintype "passive"))
    )
    (net (code "38") (name "Net-(IC2A--IN)") (class "Default")
      (node (ref "IC2") (pin "2") (pinfunction "-IN_2") (pintype "input"))
      (node (ref "R7") (pin "2") (pinfunction "2_2") (pintype "passive"))
      (node (ref "R8") (pin "1") (pinfunction "1_1") (pintype "passive"))
    )
    (net (code "39") (name "Net-(IC2A-OUT)") (class "Default")
      (node (ref "D1") (pin "A") (pinfunction "A_A") (pintype "passive"))
      (node (ref "IC2") (pin "1") (pinfunction "OUT_1") (pintype "output"))
      (node (ref "R8") (pin "2") (pinfunction "2_2") (pintype "passive"))
    )
    (net (code "40") (name "Net-(IC2B--IN)") (class "Default")
      (node (ref "IC2") (pin "6") (pinfunction "-IN_6") (pintype "input"))
      (node (ref "R13") (pin "2") (pinfunction "2_2") (pintype "passive"))
      (node (ref "R14") (pin "1") (pinfunction "1_1") (pintype "passive"))
    )
    (net (code "41") (name "Net-(IC2B-OUT)") (class "Default")
      (node (ref "D2") (pin "A") (pinfunction "A_A") (pintype "passive"))
      (node (ref "IC2") (pin "7") (pinfunction "OUT_7") (pintype "output"))
      (node (ref "R14") (pin "2") (pinfunction "2_2") (pintype "passive"))
    )
    (net (code "42") (name "Net-(IC2C--IN)") (class "Default")
      (node (ref "IC2") (pin "9") (pinfunction "-IN_9") (pintype "input"))
      (node (ref "R17") (pin "2") (pinfunction "2_2") (pintype "passive"))
      (node (ref "R18") (pin "1") (pinfunction "1_1") (pintype "passive"))
    )
    (net (code "43") (name "Net-(IC2C-OUT)") (class "Default")
      (node (ref "D3") (pin "A") (pinfunction "A_A") (pintype "passive"))
      (node (ref "IC2") (pin "8") (pinfunction "OUT_8") (pintype "output"))
      (node (ref "R18") (pin "2") (pinfunction "2_2") (pintype "passive"))
    )
    (net (code "44") (name "Net-(IC2D--IN)") (class "Default")
      (node (ref "IC2") (pin "13") (pinfunction "-IN_13") (pintype "input"))
      (node (ref "R21") (pin "2") (pinfunction "2_2") (pintype "passive"))
      (node (ref "R22") (pin "1") (pinfunction "1_1") (pintype "passive"))
    )
    (net (code "45") (name "Net-(IC2D-OUT)") (class "Default")
      (node (ref "D4") (pin "A") (pinfunction "A_A") (pintype "passive"))
      (node (ref "IC2") (pin "14") (pinfunction "OUT_14") (pintype "output"))
      (node (ref "R22") (pin "2") (pinfunction "2_2") (pintype "passive"))
    )
    (net (code "46") (name "Net-(IC3--IN)") (class "Default")
      (node (ref "IC3") (pin "2") (pinfunction "-IN_2") (pintype "input"))
      (node (ref "R6") (pin "2") (pinfunction "2_2") (pintype "passive"))
    )
    (net (code "47") (name "Net-(IC4--IN)") (class "Default")
      (node (ref "IC4") (pin "2") (pinfunction "-IN_2") (pintype "input"))
      (node (ref "R25") (pin "2") (pinfunction "2_2") (pintype "passive"))
      (node (ref "R26") (pin "1") (pinfunction "1_1") (pintype "passive"))
    )
    (net (code "48") (name "Net-(IC4-OUT)") (class "Default")
      (node (ref "D5") (pin "A") (pinfunction "A_A") (pintype "passive"))
      (node (ref "IC4") (pin "6") (pinfunction "OUT_6") (pintype "output"))
      (node (ref "R26") (pin "2") (pinfunction "2_2") (pintype "passive"))
    )
    (net (code "49") (name "Net-(LED1-PadA)") (class "Default")
      (node (ref "LED1") (pin "A") (pinfunction "A_A") (pintype "passive"))
      (node (ref "R38") (pin "1") (pinfunction "1_1") (pintype "passive"))
    )
    (net (code "50") (name "Net-(LED2-PadA)") (class "Default")
      (node (ref "LED2") (pin "A") (pinfunction "A_A") (pintype "passive"))
      (node (ref "R36") (pin "1") (pinfunction "1_1") (pintype "passive"))
    )
    (net (code "51") (name "Net-(LED3-PadA)") (class "Default")
      (node (ref "LED3") (pin "A") (pinfunction "A_A") (pintype "passive"))
      (node (ref "R34") (pin "1") (pinfunction "1_1") (pintype "passive"))
    )
    (net (code "52") (name "Net-(LED4-PadA)") (class "Default")
      (node (ref "LED4") (pin "A") (pinfunction "A_A") (pintype "passive"))
      (node (ref "R32") (pin "1") (pinfunction "1_1") (pintype "passive"))
    )
    (net (code "53") (name "Net-(LED5-PadA)") (class "Default")
      (node (ref "LED5") (pin "A") (pinfunction "A_A") (pintype "passive"))
      (node (ref "R30") (pin "1") (pinfunction "1_1") (pintype "passive"))
    )
    (net (code "54") (name "Net-(LED6-PadC)") (class "Default")
      (node (ref "LED6") (pin "C") (pinfunction "C_C") (pintype "passive"))
      (node (ref "R40") (pin "2") (pinfunction "2_2") (pintype "passive"))
    )
    (net (code "55") (name "Net-(R10-Pad2)") (class "Default")
      (node (ref "R10") (pin "2") (pinfunction "2_2") (pintype "passive"))
      (node (ref "R11") (pin "2") (pinfunction "2_2") (pintype "passive"))
      (node (ref "R4") (pin "1") (pinfunction "1_1") (pintype "passive"))
    )
    (net (code "56") (name "Net-(U1-C+)") (class "Default")
      (node (ref "C5") (pin "+") (pinfunction "+_+") (pintype "passive"))
      (node (ref "U1") (pin "6") (pinfunction "C+_6") (pintype "passive"))
    )
    (net (code "57") (name "Net-(U1-C-)") (class "Default")
      (node (ref "C5") (pin "-") (pinfunction "-_-") (pintype "passive"))
      (node (ref "U1") (pin "3") (pinfunction "C-_3") (pintype "passive"))
    )
    (net (code "58") (name "Net-(U5-BYPASS)") (class "Default")
      (node (ref "C1") (pin "1") (pinfunction "1_1") (pintype "passive"))
      (node (ref "U5") (pin "6") (pinfunction "BYPASS_6") (pintype "input"))
    )
    (net (code "59") (name "Net-(XB1-ASSOC{slash}AD5{slash}DIO5)") (class "Default")
      (node (ref "LED6") (pin "A") (pinfunction "A_A") (pintype "passive"))
      (node (ref "XB1") (pin "15") (pinfunction "ASSOC/AD5/DIO5_15") (pintype "bidirectional"))
    )
    (net (code "60") (name "Net-(XB1-DIN{slash}~{CONFIG})") (class "Default")
      (node (ref "R2") (pin "2") (pinfunction "2_2") (pintype "passive"))
      (node (ref "XB1") (pin "3") (pinfunction "DIN/~{CONFIG}_3") (pintype "input"))
    )
    (net (code "61") (name "Net-(XB1-DOUT)") (class "Default")
      (node (ref "R3") (pin "2") (pinfunction "2_2") (pintype "passive"))
      (node (ref "XB1") (pin "2") (pinfunction "DOUT_2") (pintype "output"))
    )
    (net (code "62") (name "Net-(XB1-~{RESET})") (class "Default")
      (node (ref "R1") (pin "2") (pinfunction "2_2") (pintype "passive"))
      (node (ref "XB1") (pin "5") (pinfunction "~{RESET}_5") (pintype "input"))
    )
    (net (code "63") (name "unconnected-(IC3-+IN-Pad3)") (class "Default")
      (node (ref "IC3") (pin "3") (pinfunction "+IN_3") (pintype "input"))
    )
    (net (code "64") (name "unconnected-(KIT1-P5-PadP$5)") (class "Default")
      (node (ref "KIT1") (pin "P$5") (pinfunction "P5_P$5") (pintype "bidirectional"))
    )
    (net (code "65") (name "unconnected-(KIT1-P6-PadP$6)") (class "Default")
      (node (ref "KIT1") (pin "P$6") (pinfunction "P6_P$6") (pintype "bidirectional"))
    )
    (net (code "66") (name "unconnected-(KIT1-P7-PadP$7)") (class "Default")
      (node (ref "KIT1") (pin "P$7") (pinfunction "P7_P$7") (pintype "bidirectional"))
    )
    (net (code "67") (name "unconnected-(KIT1-P8-PadP$8)") (class "Default")
      (node (ref "KIT1") (pin "P$8") (pinfunction "P8_P$8") (pintype "bidirectional"))
    )
    (net (code "68") (name "unconnected-(KIT1-P11-PadP$11)") (class "Default")
      (node (ref "KIT1") (pin "P$11") (pinfunction "P11_P$11") (pintype "bidirectional"))
    )
    (net (code "69") (name "unconnected-(KIT1-P13-PadP$13)") (class "Default")
      (node (ref "KIT1") (pin "P$13") (pinfunction "P13_P$13") (pintype "bidirectional"))
    )
    (net (code "70") (name "unconnected-(KIT1-P14-PadP$14)") (class "Default")
      (node (ref "KIT1") (pin "P$14") (pinfunction "P14_P$14") (pintype "bidirectional"))
    )
    (net (code "71") (name "unconnected-(KIT1-P23-PadP$23)") (class "Default")
      (node (ref "KIT1") (pin "P$23") (pinfunction "P23_P$23") (pintype "bidirectional"))
    )
    (net (code "72") (name "unconnected-(KIT1-P24-PadP$24)") (class "Default")
      (node (ref "KIT1") (pin "P$24") (pinfunction "P24_P$24") (pintype "bidirectional"))
    )
    (net (code "73") (name "unconnected-(KIT1-P25-PadP$25)") (class "Default")
      (node (ref "KIT1") (pin "P$25") (pinfunction "P25_P$25") (pintype "bidirectional"))
    )
    (net (code "74") (name "unconnected-(KIT1-P27-PadP$27)") (class "Default")
      (node (ref "KIT1") (pin "P$27") (pinfunction "P27_P$27") (pintype "bidirectional"))
    )
    (net (code "75") (name "unconnected-(KIT1-P28-PadP$28)") (class "Default")
      (node (ref "KIT1") (pin "P$28") (pinfunction "P28_P$28") (pintype "bidirectional"))
    )
    (net (code "76") (name "unconnected-(KIT1-P29-PadP$29)") (class "Default")
      (node (ref "KIT1") (pin "P$29") (pinfunction "P29_P$29") (pintype "bidirectional"))
    )
    (net (code "77") (name "unconnected-(KIT1-P30-PadP$30)") (class "Default")
      (node (ref "KIT1") (pin "P$30") (pinfunction "P30_P$30") (pintype "bidirectional"))
    )
    (net (code "78") (name "unconnected-(KIT1-PadD+)") (class "Default")
      (node (ref "KIT1") (pin "D+") (pinfunction "D+_D+") (pintype "bidirectional"))
    )
    (net (code "79") (name "unconnected-(KIT1-PadIF+)") (class "Default")
      (node (ref "KIT1") (pin "IF+") (pinfunction "IF+_IF+") (pintype "bidirectional"))
    )
    (net (code "80") (name "unconnected-(KIT1-PadIF-)") (class "Default")
      (node (ref "KIT1") (pin "IF-") (pinfunction "IF-_IF-") (pintype "bidirectional"))
    )
    (net (code "81") (name "unconnected-(U4-IN3-Pad4)") (class "Default")
      (node (ref "U4") (pin "4") (pinfunction "IN3_4") (pintype "bidirectional"))
    )
    (net (code "82") (name "unconnected-(U4-IN4-Pad5)") (class "Default")
      (node (ref "U4") (pin "5") (pinfunction "IN4_5") (pintype "bidirectional"))
    )
    (net (code "83") (name "unconnected-(U5-NC-Pad8)") (class "Default")
      (node (ref "U5") (pin "8") (pinfunction "NC_8") (pintype "no_connect"))
    )
    (net (code "84") (name "unconnected-(U5-NC_2-Pad3)") (class "Default")
      (node (ref "U5") (pin "3") (pinfunction "NC_2_3") (pintype "no_connect"))
    )
    (net (code "85") (name "unconnected-(XB1-AD0{slash}DIO0-Pad20)") (class "Default")
      (node (ref "XB1") (pin "20") (pinfunction "AD0/DIO0_20") (pintype "bidirectional"))
    )
    (net (code "86") (name "unconnected-(XB1-AD1{slash}DIO1-Pad19)") (class "Default")
      (node (ref "XB1") (pin "19") (pinfunction "AD1/DIO1_19") (pintype "bidirectional"))
    )
    (net (code "87") (name "unconnected-(XB1-AD2{slash}DIO2-Pad18)") (class "Default")
      (node (ref "XB1") (pin "18") (pinfunction "AD2/DIO2_18") (pintype "bidirectional"))
    )
    (net (code "88") (name "unconnected-(XB1-CD{slash}DOUT_EN{slash}DO8-Pad4)") (class "Default")
      (node (ref "XB1") (pin "4") (pinfunction "CD/DOUT_EN/DO8_4") (pintype "output"))
    )
    (net (code "89") (name "unconnected-(XB1-COORD_SEL{slash}AD3{slash}DIO3-Pad17)") (class "Default")
      (node (ref "XB1") (pin "17") (pinfunction "COORD_SEL/AD3/DIO3_17") (pintype "bidirectional"))
    )
    (net (code "90") (name "unconnected-(XB1-ON{slash}~{SLEEP}-Pad13)") (class "Default")
      (node (ref "XB1") (pin "13") (pinfunction "ON/~{SLEEP}_13") (pintype "output"))
    )
    (net (code "91") (name "unconnected-(XB1-PWM0{slash}RSSI-Pad6)") (class "Default")
      (node (ref "XB1") (pin "6") (pinfunction "PWM0/RSSI_6") (pintype "output"))
    )
    (net (code "92") (name "unconnected-(XB1-RF_TX{slash}AD4{slash}DIO4-Pad11)") (class "Default")
      (node (ref "XB1") (pin "11") (pinfunction "RF_TX/AD4/DIO4_11") (pintype "bidirectional"))
    )
    (net (code "93") (name "unconnected-(XB1-VREF-Pad14)") (class "Default")
      (node (ref "XB1") (pin "14") (pinfunction "VREF_14") (pintype "input"))
    )
    (net (code "94") (name "unconnected-(XB1-~{CTS}{slash}DIO7-Pad12)") (class "Default")
      (node (ref "XB1") (pin "12") (pinfunction "~{CTS}/DIO7_12") (pintype "bidirectional"))
    )
    (net (code "95") (name "unconnected-(XB1-~{DTR}{slash}SLEEP_RQ{slash}DI8-Pad9)") (class "Default")
      (node (ref "XB1") (pin "9") (pinfunction "~{DTR}/SLEEP_RQ/DI8_9") (pintype "bidirectional"))
    )
    (net (code "96") (name "unconnected-(XB1-~{RTS}{slash}AD6{slash}DIO6-Pad16)") (class "Default")
      (node (ref "XB1") (pin "16") (pinfunction "~{RTS}/AD6/DIO6_16") (pintype "bidirectional"))
    )
  )
)
